# Interfaces.net
KiCad netlist of a schematic drawn in Altium Designer
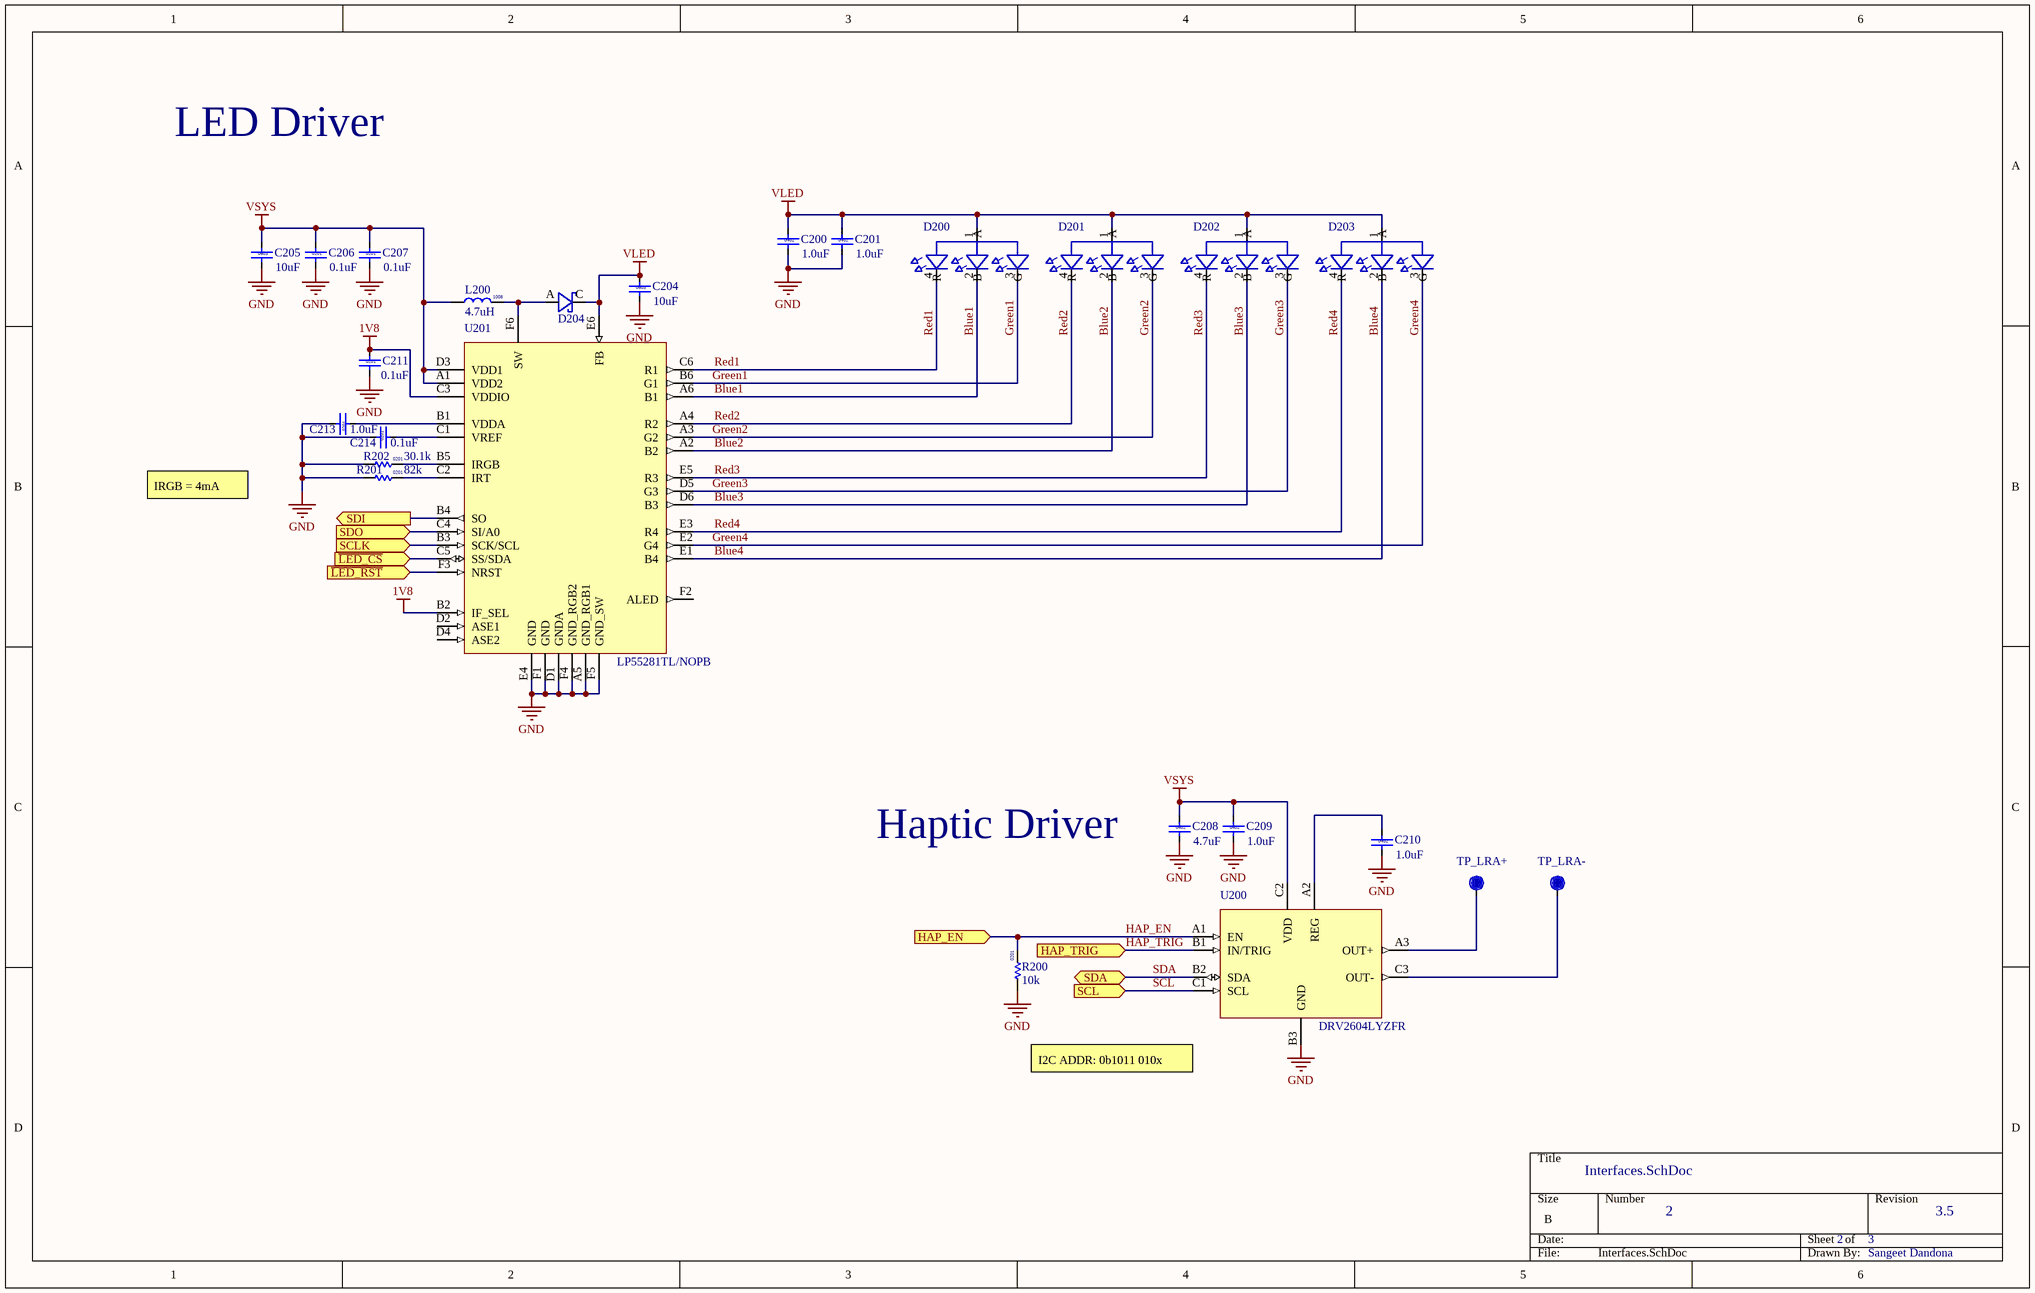
[diagram p0: Interfaces.SchDoc]

(export (version "E")
  (design (tool "Eeschema 10.0.6"))
  (components
    (comp (ref "C200")
      (value "1.0uF")
      (footprint "Cap 0402 HD")
      (description "CAP CER 1UF 10V 10% X5R 0402")
      (fields (field (name "SIZE") "0402") (field (name "MF") "Murata Electronics North America"))
      (libsource (lib "Rigado_AltiumLib") (part "Cap Chip"))
    )
    (comp (ref "C201")
      (value "1.0uF")
      (footprint "Cap 0402 HD")
      (description "CAP CER 1UF 10V 10% X5R 0402")
      (fields (field (name "SIZE") "0402") (field (name "MF") "Murata Electronics North America"))
      (libsource (lib "Rigado_AltiumLib") (part "Cap Chip"))
    )
    (comp (ref "C204")
      (value "10uF")
      (footprint "Cap 0603")
      (description "CAP CER 10UF 10V 20% X5R 0603")
      (fields (field (name "SIZE") "0603") (field (name "MF") "TDK Corporation"))
      (libsource (lib "Rigado_AltiumLib") (part "Cap Chip"))
    )
    (comp (ref "C205")
      (value "10uF")
      (footprint "Cap 0603")
      (description "CAP CER 10UF 10V 20% X5R 0603")
      (fields (field (name "SIZE") "0603") (field (name "MF") "TDK Corporation"))
      (libsource (lib "Rigado_AltiumLib") (part "Cap Chip"))
    )
    (comp (ref "C206")
      (value "0.1uF")
      (footprint "Cap 0201 HD")
      (description "CAP CER 0.1UF 6.3V 10% X5R 0201")
      (fields (field (name "SIZE") "0201") (field (name "MF") "Murata Electronics North America"))
      (libsource (lib "Rigado_AltiumLib") (part "Cap Chip"))
    )
    (comp (ref "C207")
      (value "0.1uF")
      (footprint "Cap 0201 HD")
      (description "CAP CER 0.1UF 6.3V 10% X5R 0201")
      (fields (field (name "SIZE") "0201") (field (name "MF") "Murata Electronics North America"))
      (libsource (lib "Rigado_AltiumLib") (part "Cap Chip"))
    )
    (comp (ref "C208")
      (value "4.7uF")
      (footprint "Cap 0402 HD")
      (description "CAP CER 4.7UF 10V 20% X5R 0402")
      (fields (field (name "SIZE") "0402") (field (name "MF") "Samsung Electro-Mechanics America, Inc."))
      (libsource (lib "Rigado_AltiumLib") (part "Cap Chip"))
    )
    (comp (ref "C209")
      (value "1.0uF")
      (footprint "Cap 0402 HD")
      (description "CAP CER 1UF 10V 10% X5R 0402")
      (fields (field (name "SIZE") "0402") (field (name "MF") "Murata Electronics North America"))
      (libsource (lib "Rigado_AltiumLib") (part "Cap Chip"))
    )
    (comp (ref "C210")
      (value "1.0uF")
      (footprint "Cap 0402 HD")
      (description "CAP CER 1UF 10V 10% X5R 0402")
      (fields (field (name "SIZE") "0402") (field (name "MF") "Murata Electronics North America"))
      (libsource (lib "Rigado_AltiumLib") (part "Cap Chip"))
    )
    (comp (ref "C211")
      (value "0.1uF")
      (footprint "Cap 0201 HD")
      (description "CAP CER 0.1UF 6.3V 10% X5R 0201")
      (fields (field (name "SIZE") "0201") (field (name "MF") "Murata Electronics North America"))
      (libsource (lib "Rigado_AltiumLib") (part "Cap Chip"))
    )
    (comp (ref "C213")
      (value "1.0uF")
      (footprint "Cap 0201 HD")
      (description "CAP CER 1UF 6.3V 20% X5R 0201")
      (fields (field (name "SIZE") "0201") (field (name "MF") "Samsung Electro-Mechanics America, Inc."))
      (libsource (lib "Rigado_AltiumLib") (part "Cap Chip"))
    )
    (comp (ref "C214")
      (value "0.1uF")
      (footprint "Cap 0201 HD")
      (description "CAP CER 0.1UF 6.3V 10% X5R 0201")
      (fields (field (name "SIZE") "0201") (field (name "MF") "Murata Electronics North America"))
      (libsource (lib "Rigado_AltiumLib") (part "Cap Chip"))
    )
    (comp (ref "D200")
      (value "~")
      (footprint "4-PLCC")
      (description "LED RGB 3-IN-1 SMD 4PLCC")
      (fields (field (name "MF") "Cree Inc."))
      (libsource (lib "Rigado_AltiumLib") (part "LED_RGB_CA_2"))
    )
    (comp (ref "D201")
      (value "~")
      (footprint "4-PLCC")
      (description "LED RGB 3-IN-1 SMD 4PLCC")
      (fields (field (name "MF") "Cree Inc."))
      (libsource (lib "Rigado_AltiumLib") (part "LED_RGB_CA_2"))
    )
    (comp (ref "D202")
      (value "~")
      (footprint "4-PLCC")
      (description "LED RGB 3-IN-1 SMD 4PLCC")
      (fields (field (name "MF") "Cree Inc."))
      (libsource (lib "Rigado_AltiumLib") (part "LED_RGB_CA_2"))
    )
    (comp (ref "D203")
      (value "~")
      (footprint "4-PLCC")
      (description "LED RGB 3-IN-1 SMD 4PLCC")
      (fields (field (name "MF") "Cree Inc."))
      (libsource (lib "Rigado_AltiumLib") (part "LED_RGB_CA_2"))
    )
    (comp (ref "D204")
      (value "~")
      (footprint "SOD-123F_U")
      (description "DIODE SCHOTTKY 20V 1A SOD123FL")
      (fields (field (name "MF") "ON Semiconductor"))
      (libsource (lib "LOCAL_Rigado_AltiumLib") (part "Diode_Schottky"))
    )
    (comp (ref "L200")
      (value "4.7uH")
      (footprint "IND 1008")
      (description "FIXED IND 4.7UH 1A 250 MOHM SMD")
      (fields (field (name "SIZE") "1008") (field (name "MF") "Samsung Electro-Mechanics America, Inc."))
      (libsource (lib "Rigado_AltiumLib") (part "Ind sm"))
    )
    (comp (ref "R200")
      (value "10k")
      (footprint "RES 0201 HD")
      (description "RES SMD 10K OHM 5% 1/20W 0201")
      (fields (field (name "SIZE") "0201") (field (name "MF") "Rohm Semiconductor"))
      (libsource (lib "Rigado_AltiumLib") (part "Res sm"))
    )
    (comp (ref "R201")
      (value "82k")
      (footprint "RES 0201 HD")
      (description "RES SMD 82K OHM 1% 1/20W 0201")
      (fields (field (name "SIZE") "0201") (field (name "MF") "Panasonic Electronic Components"))
      (libsource (lib "Rigado_AltiumLib") (part "Res sm"))
    )
    (comp (ref "R202")
      (value "30.1k")
      (footprint "RES 0201 HD")
      (description "RES SMD 30.1K OHM 1% 1/20W 0201")
      (fields (field (name "SIZE") "0201") (field (name "MF") "Panasonic Electronic Components"))
      (libsource (lib "Rigado_AltiumLib") (part "Res sm"))
    )
    (comp (ref "TP_LRA+")
      (value "TP")
      (footprint "TP17R")
      (description "Testpoint, Round 1.7mm Dia")
      (libsource (lib "LOCAL_Rigado_AltiumLib") (part "TP_R"))
    )
    (comp (ref "TP_LRA-")
      (value "TP")
      (footprint "TP17R")
      (description "Testpoint, Round 1.7mm Dia")
      (libsource (lib "LOCAL_Rigado_AltiumLib") (part "TP_R"))
    )
    (comp (ref "U200")
      (value "~")
      (footprint "BGA0.5P3x3-9Pin")
      (description "IC ERM/LRA HAPTIC DRIVER 9DSBGA")
      (fields (field (name "MF") "Texas Instruments") (field (name "MFPN") "DRV2604LYZFR"))
      (libsource (lib "Rigado_AltiumLib") (part "DRV2604L"))
    )
    (comp (ref "U201")
      (value "~")
      (footprint "BGA0.5P6x6-36Pin")
      (description "IC LED DRIVER RGLTR DIM 36USMD")
      (fields (field (name "MF") "Texas Instruments") (field (name "MFPN") "LP55281TL/NOPB"))
      (libsource (lib "Rigado_AltiumLib") (part "LP55281"))
    )
  )
  (nets
    (net (code "1") (name "/Blue1") (class "Default")
      (node (ref "D200") (pin "2") (pinfunction "B_2") (pintype "passive"))
      (node (ref "U201") (pin "A6") (pinfunction "B1_A6") (pintype "output"))
    )
    (net (code "2") (name "/Blue2") (class "Default")
      (node (ref "D201") (pin "2") (pinfunction "B_2") (pintype "passive"))
      (node (ref "U201") (pin "A2") (pinfunction "B2_A2") (pintype "output"))
    )
    (net (code "3") (name "/Blue3") (class "Default")
      (node (ref "D202") (pin "2") (pinfunction "B_2") (pintype "passive"))
      (node (ref "U201") (pin "D6") (pinfunction "B3_D6") (pintype "output"))
    )
    (net (code "4") (name "/Blue4") (class "Default")
      (node (ref "D203") (pin "2") (pinfunction "B_2") (pintype "passive"))
      (node (ref "U201") (pin "E1") (pinfunction "B4_E1") (pintype "output"))
    )
    (net (code "5") (name "/Green1") (class "Default")
      (node (ref "D200") (pin "3") (pinfunction "G_3") (pintype "passive"))
      (node (ref "U201") (pin "B6") (pinfunction "G1_B6") (pintype "output"))
    )
    (net (code "6") (name "/Green2") (class "Default")
      (node (ref "D201") (pin "3") (pinfunction "G_3") (pintype "passive"))
      (node (ref "U201") (pin "A3") (pinfunction "G2_A3") (pintype "output"))
    )
    (net (code "7") (name "/Green3") (class "Default")
      (node (ref "D202") (pin "3") (pinfunction "G_3") (pintype "passive"))
      (node (ref "U201") (pin "D5") (pinfunction "G3_D5") (pintype "output"))
    )
    (net (code "8") (name "/Green4") (class "Default")
      (node (ref "D203") (pin "3") (pinfunction "G_3") (pintype "passive"))
      (node (ref "U201") (pin "E2") (pinfunction "G4_E2") (pintype "output"))
    )
    (net (code "9") (name "/HAP_EN") (class "Default")
      (node (ref "R200") (pin "2") (pinfunction "2_2") (pintype "passive"))
      (node (ref "U200") (pin "A1") (pinfunction "EN_A1") (pintype "input"))
    )
    (net (code "10") (name "/HAP_TRIG") (class "Default")
      (node (ref "U200") (pin "B1") (pinfunction "IN/TRIG_B1") (pintype "input"))
    )
    (net (code "11") (name "/LED_CS") (class "Default")
      (node (ref "U201") (pin "C5") (pinfunction "SS/SDA_C5") (pintype "bidirectional"))
    )
    (net (code "12") (name "/LED_RST") (class "Default")
      (node (ref "U201") (pin "F3") (pinfunction "NRST_F3") (pintype "input"))
    )
    (net (code "13") (name "/Red1") (class "Default")
      (node (ref "D200") (pin "4") (pinfunction "R_4") (pintype "passive"))
      (node (ref "U201") (pin "C6") (pinfunction "R1_C6") (pintype "output"))
    )
    (net (code "14") (name "/Red2") (class "Default")
      (node (ref "D201") (pin "4") (pinfunction "R_4") (pintype "passive"))
      (node (ref "U201") (pin "A4") (pinfunction "R2_A4") (pintype "output"))
    )
    (net (code "15") (name "/Red3") (class "Default")
      (node (ref "D202") (pin "4") (pinfunction "R_4") (pintype "passive"))
      (node (ref "U201") (pin "E5") (pinfunction "R3_E5") (pintype "output"))
    )
    (net (code "16") (name "/Red4") (class "Default")
      (node (ref "D203") (pin "4") (pinfunction "R_4") (pintype "passive"))
      (node (ref "U201") (pin "E3") (pinfunction "R4_E3") (pintype "output"))
    )
    (net (code "17") (name "/SCL") (class "Default")
      (node (ref "U200") (pin "C1") (pinfunction "SCL_C1") (pintype "input"))
    )
    (net (code "18") (name "/SCLK") (class "Default")
      (node (ref "U201") (pin "B3") (pinfunction "SCK/SCL_B3") (pintype "input"))
    )
    (net (code "19") (name "/SDA") (class "Default")
      (node (ref "U200") (pin "B2") (pinfunction "SDA_B2") (pintype "bidirectional"))
    )
    (net (code "20") (name "/SDI") (class "Default")
      (node (ref "U201") (pin "B4") (pinfunction "SO_B4") (pintype "output"))
    )
    (net (code "21") (name "/SDO") (class "Default")
      (node (ref "U201") (pin "C4") (pinfunction "SI/A0_C4") (pintype "input"))
    )
    (net (code "22") (name "1V8") (class "Default")
      (node (ref "C211") (pin "1") (pinfunction "1_1") (pintype "passive"))
      (node (ref "U201") (pin "B2") (pinfunction "IF_SEL_B2") (pintype "input"))
      (node (ref "U201") (pin "C3") (pinfunction "VDDIO_C3") (pintype "power_in"))
    )
    (net (code "23") (name "GND") (class "Default")
      (node (ref "C200") (pin "2") (pinfunction "2_2") (pintype "passive"))
      (node (ref "C201") (pin "2") (pinfunction "2_2") (pintype "passive"))
      (node (ref "C204") (pin "2") (pinfunction "2_2") (pintype "passive"))
      (node (ref "C205") (pin "2") (pinfunction "2_2") (pintype "passive"))
      (node (ref "C206") (pin "2") (pinfunction "2_2") (pintype "passive"))
      (node (ref "C207") (pin "2") (pinfunction "2_2") (pintype "passive"))
      (node (ref "C208") (pin "2") (pinfunction "2_2") (pintype "passive"))
      (node (ref "C209") (pin "2") (pinfunction "2_2") (pintype "passive"))
      (node (ref "C210") (pin "2") (pinfunction "2_2") (pintype "passive"))
      (node (ref "C211") (pin "2") (pinfunction "2_2") (pintype "passive"))
      (node (ref "C213") (pin "2") (pinfunction "2_2") (pintype "passive"))
      (node (ref "C214") (pin "1") (pinfunction "1_1") (pintype "passive"))
      (node (ref "R200") (pin "1") (pinfunction "1_1") (pintype "passive"))
      (node (ref "R201") (pin "1") (pinfunction "1_1") (pintype "passive"))
      (node (ref "R202") (pin "1") (pinfunction "1_1") (pintype "passive"))
      (node (ref "U200") (pin "B3") (pinfunction "GND_B3") (pintype "power_in"))
      (node (ref "U201") (pin "A5") (pinfunction "GND_RGB1_A5") (pintype "power_in"))
      (node (ref "U201") (pin "D1") (pinfunction "GNDA_D1") (pintype "power_in"))
      (node (ref "U201") (pin "E4") (pinfunction "GND_E4") (pintype "power_in"))
      (node (ref "U201") (pin "F1") (pinfunction "GND_F1") (pintype "power_in"))
      (node (ref "U201") (pin "F4") (pinfunction "GND_RGB2_F4") (pintype "power_in"))
      (node (ref "U201") (pin "F5") (pinfunction "GND_SW_F5") (pintype "power_in"))
    )
    (net (code "24") (name "Net-(U200-OUT+)") (class "Default")
      (node (ref "TP_LRA+") (pin "1") (pintype "passive"))
      (node (ref "U200") (pin "A3") (pinfunction "OUT+_A3") (pintype "output"))
    )
    (net (code "25") (name "Net-(U200-OUT-)") (class "Default")
      (node (ref "TP_LRA-") (pin "1") (pintype "passive"))
      (node (ref "U200") (pin "C3") (pinfunction "OUT-_C3") (pintype "output"))
    )
    (net (code "26") (name "Net-(U200-REG)") (class "Default")
      (node (ref "C210") (pin "1") (pinfunction "1_1") (pintype "passive"))
      (node (ref "U200") (pin "A2") (pinfunction "REG_A2") (pintype "power_in"))
    )
    (net (code "27") (name "Net-(U201-IRGB)") (class "Default")
      (node (ref "R202") (pin "2") (pinfunction "2_2") (pintype "passive"))
      (node (ref "U201") (pin "B5") (pinfunction "IRGB_B5") (pintype "passive"))
    )
    (net (code "28") (name "Net-(U201-IRT)") (class "Default")
      (node (ref "R201") (pin "2") (pinfunction "2_2") (pintype "passive"))
      (node (ref "U201") (pin "C2") (pinfunction "IRT_C2") (pintype "passive"))
    )
    (net (code "29") (name "Net-(U201-SW)") (class "Default")
      (node (ref "D204") (pin "A") (pintype "passive"))
      (node (ref "L200") (pin "2") (pinfunction "2_2") (pintype "passive"))
      (node (ref "U201") (pin "F6") (pinfunction "SW_F6") (pintype "power_in"))
    )
    (net (code "30") (name "Net-(U201-VDDA)") (class "Default")
      (node (ref "C213") (pin "1") (pinfunction "1_1") (pintype "passive"))
      (node (ref "U201") (pin "B1") (pinfunction "VDDA_B1") (pintype "power_in"))
    )
    (net (code "31") (name "Net-(U201-VREF)") (class "Default")
      (node (ref "C214") (pin "2") (pinfunction "2_2") (pintype "passive"))
      (node (ref "U201") (pin "C1") (pinfunction "VREF_C1") (pintype "passive"))
    )
    (net (code "32") (name "VLED") (class "Default")
      (node (ref "C200") (pin "1") (pinfunction "1_1") (pintype "passive"))
      (node (ref "C201") (pin "1") (pinfunction "1_1") (pintype "passive"))
      (node (ref "C204") (pin "1") (pinfunction "1_1") (pintype "passive"))
      (node (ref "D200") (pin "1") (pinfunction "A_1") (pintype "passive"))
      (node (ref "D201") (pin "1") (pinfunction "A_1") (pintype "passive"))
      (node (ref "D202") (pin "1") (pinfunction "A_1") (pintype "passive"))
      (node (ref "D203") (pin "1") (pinfunction "A_1") (pintype "passive"))
      (node (ref "D204") (pin "C") (pintype "passive"))
      (node (ref "U201") (pin "E6") (pinfunction "FB_E6") (pintype "input"))
    )
    (net (code "33") (name "VSYS") (class "Default")
      (node (ref "C205") (pin "1") (pinfunction "1_1") (pintype "passive"))
      (node (ref "C206") (pin "1") (pinfunction "1_1") (pintype "passive"))
      (node (ref "C207") (pin "1") (pinfunction "1_1") (pintype "passive"))
      (node (ref "C208") (pin "1") (pinfunction "1_1") (pintype "passive"))
      (node (ref "C209") (pin "1") (pinfunction "1_1") (pintype "passive"))
      (node (ref "L200") (pin "1") (pinfunction "1_1") (pintype "passive"))
      (node (ref "U200") (pin "C2") (pinfunction "VDD_C2") (pintype "power_in"))
      (node (ref "U201") (pin "A1") (pinfunction "VDD2_A1") (pintype "power_in"))
      (node (ref "U201") (pin "D3") (pinfunction "VDD1_D3") (pintype "power_in"))
    )
    (net (code "34") (name "unconnected-(U201-ALED-PadF2)") (class "Default")
      (node (ref "U201") (pin "F2") (pinfunction "ALED_F2") (pintype "output"))
    )
    (net (code "35") (name "unconnected-(U201-ASE1-PadD2)") (class "Default")
      (node (ref "U201") (pin "D2") (pinfunction "ASE1_D2") (pintype "input"))
    )
    (net (code "36") (name "unconnected-(U201-ASE2-PadD4)") (class "Default")
      (node (ref "U201") (pin "D4") (pinfunction "ASE2_D4") (pintype "input"))
    )
  )
)
